# Autopilot2.net
KiCad netlist of a schematic drawn in EAGLE
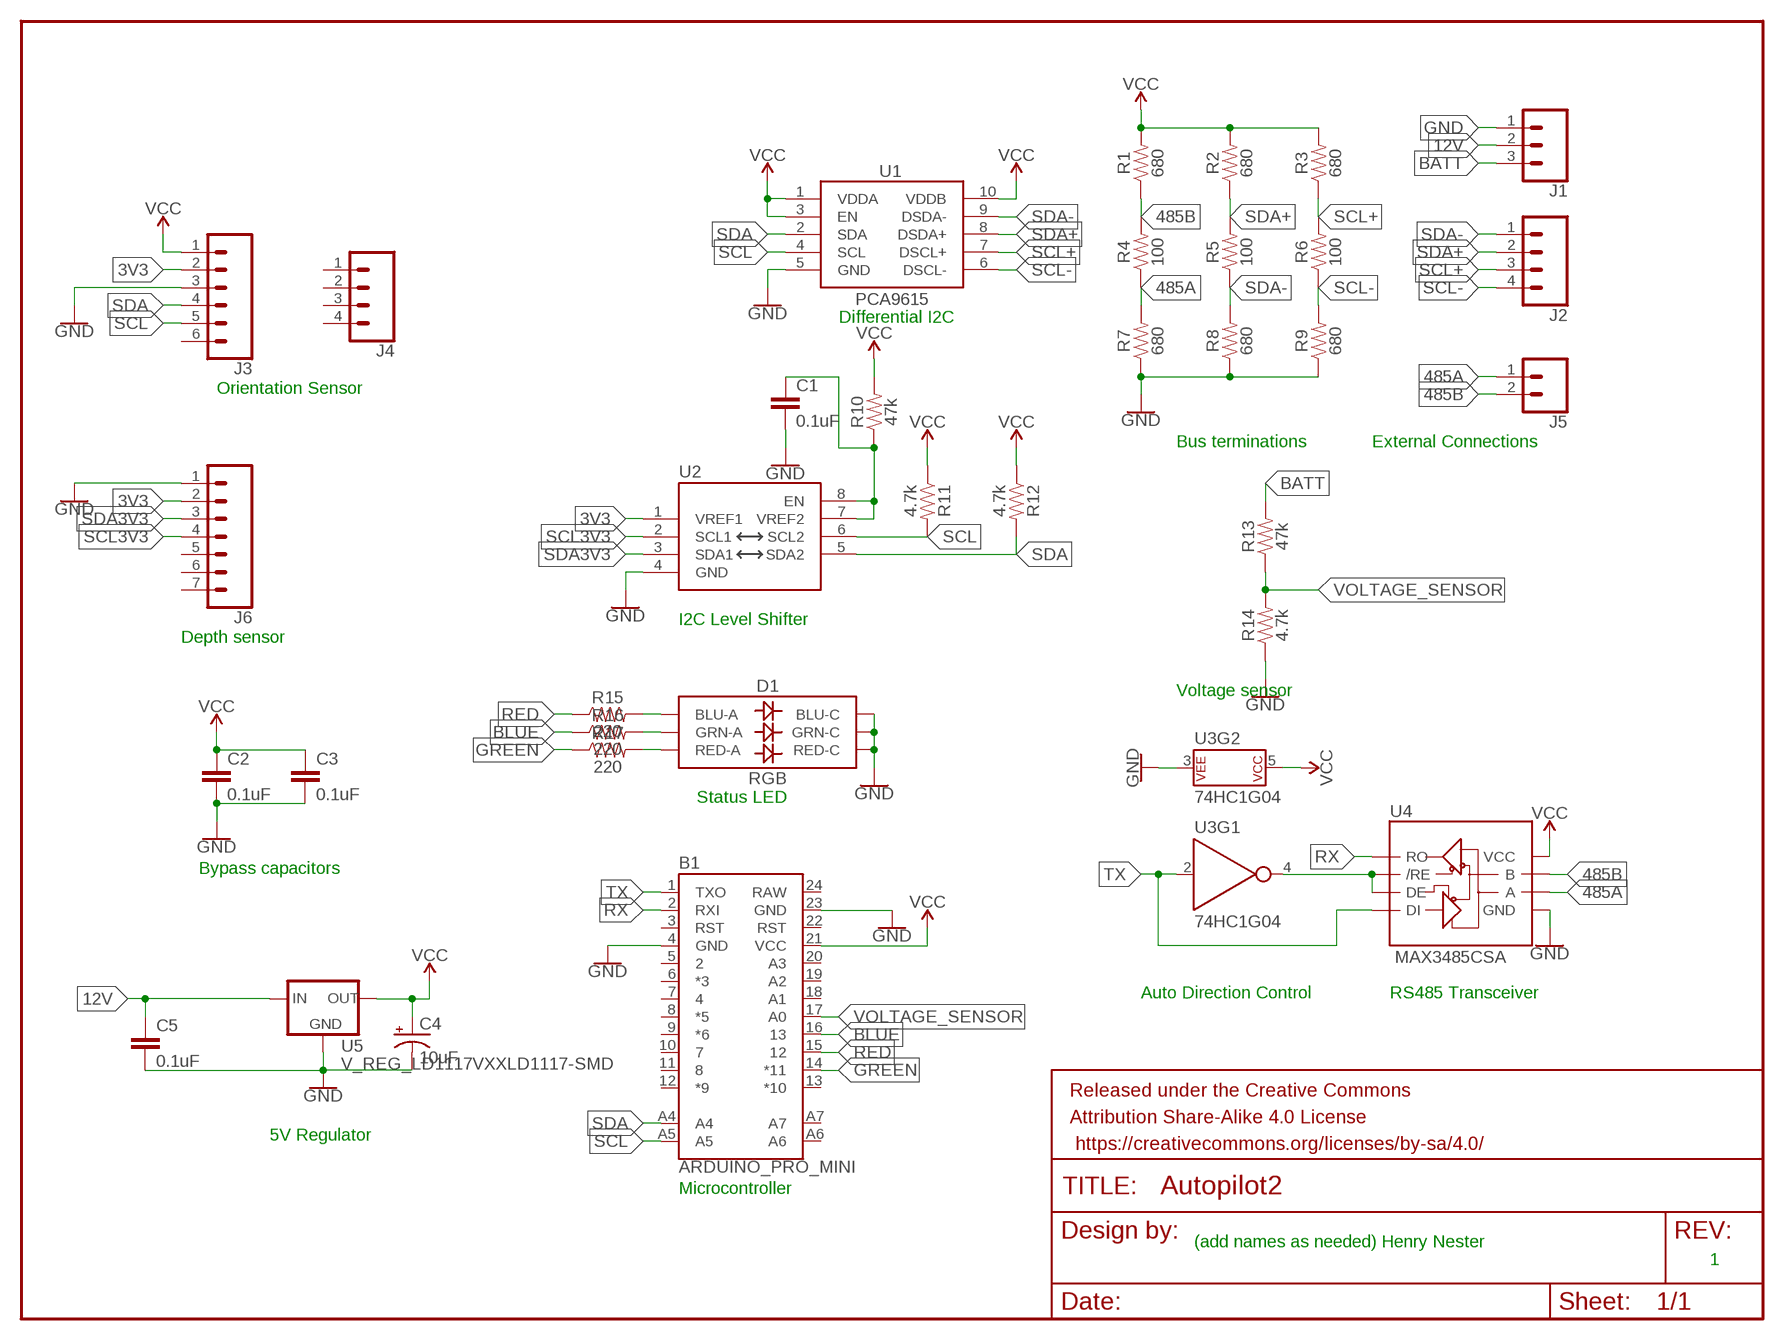
[diagram p0: schematic, sheet 1]

(export (version "E")
  (design (tool "Eeschema 10.0.6"))
  (components
    (comp (ref "B1")
      (value "ARDUINO_PRO_MINI")
      (footprint "eagle-import:ARDUINO_PRO_MINI")
      (libsource (lib "eagle-import") (part "ARDUINO_PRO_MINI"))
    )
    (comp (ref "C1")
      (value "0.1uF")
      (footprint "eagle-import:0603")
      (libsource (lib "eagle-import") (part "0.1UF-0603-25V-(+80/-20%)"))
    )
    (comp (ref "C2")
      (value "0.1uF")
      (footprint "eagle-import:0603")
      (libsource (lib "eagle-import") (part "0.1UF-0603-25V-(+80/-20%)"))
    )
    (comp (ref "C3")
      (value "0.1uF")
      (footprint "eagle-import:0603")
      (libsource (lib "eagle-import") (part "0.1UF-0603-25V-(+80/-20%)"))
    )
    (comp (ref "C4")
      (value "10uF")
      (footprint "eagle-import:CPOL-RADIAL-2.5MM-5MM")
      (libsource (lib "eagle-import") (part "10UF-POLAR-RADIAL-2.5MM-25V-20%"))
    )
    (comp (ref "C5")
      (value "0.1uF")
      (footprint "eagle-import:0603")
      (libsource (lib "eagle-import") (part "0.1UF-0603-25V-(+80/-20%)"))
    )
    (comp (ref "D1")
      (value "RGB")
      (footprint "eagle-import:PLCC-6-LED")
      (libsource (lib "eagle-import") (part "LED-RGBPLCC-6"))
    )
    (comp (ref "FRAME1")
      (value "FRAME-LETTERNO_PACKAGE")
      (footprint "eagle-import:DUMMY")
      (fields (field (name "DESIGNER") "Nobody"))
      (libsource (lib "eagle-import") (part "FRAME-LETTERNO_PACKAGE"))
    )
    (comp (ref "J1")
      (value "CONN_03LONGPADS")
      (footprint "eagle-import:1X03_LONGPADS")
      (libsource (lib "eagle-import") (part "CONN_03LONGPADS"))
    )
    (comp (ref "J2")
      (value "CONN_04")
      (footprint "eagle-import:1X04")
      (libsource (lib "eagle-import") (part "CONN_04"))
    )
    (comp (ref "J3")
      (value "CONN_06NO_SILK_FEMALE_PTH")
      (footprint "eagle-import:1X06_NO_SILK")
      (libsource (lib "eagle-import") (part "CONN_06NO_SILK_FEMALE_PTH"))
    )
    (comp (ref "J4")
      (value "CONN_041X04_NO_SILK")
      (footprint "eagle-import:1X04_NO_SILK")
      (libsource (lib "eagle-import") (part "CONN_041X04_NO_SILK"))
    )
    (comp (ref "J5")
      (value "CONN_02")
      (footprint "eagle-import:1X02")
      (libsource (lib "eagle-import") (part "CONN_02"))
    )
    (comp (ref "J6")
      (value "CONN_07NO_SILK")
      (footprint "eagle-import:1X07_NO_SILK")
      (libsource (lib "eagle-import") (part "CONN_07NO_SILK"))
    )
    (comp (ref "R1")
      (value "680")
      (footprint "eagle-import:0603")
      (libsource (lib "eagle-import") (part "680OHM-0603-1/10W-5%"))
    )
    (comp (ref "R2")
      (value "680")
      (footprint "eagle-import:0603")
      (libsource (lib "eagle-import") (part "680OHM-0603-1/10W-5%"))
    )
    (comp (ref "R3")
      (value "680")
      (footprint "eagle-import:0603")
      (libsource (lib "eagle-import") (part "680OHM-0603-1/10W-5%"))
    )
    (comp (ref "R4")
      (value "100")
      (footprint "eagle-import:0603")
      (libsource (lib "eagle-import") (part "100OHM-0603-1/4W-5%"))
    )
    (comp (ref "R5")
      (value "100")
      (footprint "eagle-import:0603")
      (libsource (lib "eagle-import") (part "100OHM-0603-1/4W-5%"))
    )
    (comp (ref "R6")
      (value "100")
      (footprint "eagle-import:0603")
      (libsource (lib "eagle-import") (part "100OHM-0603-1/4W-5%"))
    )
    (comp (ref "R7")
      (value "680")
      (footprint "eagle-import:0603")
      (libsource (lib "eagle-import") (part "680OHM-0603-1/10W-5%"))
    )
    (comp (ref "R8")
      (value "680")
      (footprint "eagle-import:0603")
      (libsource (lib "eagle-import") (part "680OHM-0603-1/10W-5%"))
    )
    (comp (ref "R9")
      (value "680")
      (footprint "eagle-import:0603")
      (libsource (lib "eagle-import") (part "680OHM-0603-1/10W-5%"))
    )
    (comp (ref "R10")
      (value "47k")
      (footprint "eagle-import:0603")
      (libsource (lib "eagle-import") (part "100KOHM-0603-1/10W-1%"))
    )
    (comp (ref "R11")
      (value "4.7k")
      (footprint "eagle-import:0603")
      (libsource (lib "eagle-import") (part "4.7KOHM-0603-1/10W-1%"))
    )
    (comp (ref "R12")
      (value "4.7k")
      (footprint "eagle-import:0603")
      (libsource (lib "eagle-import") (part "4.7KOHM-0603-1/10W-1%"))
    )
    (comp (ref "R13")
      (value "47k")
      (footprint "eagle-import:0603")
      (libsource (lib "eagle-import") (part "100KOHM-0603-1/10W-1%"))
    )
    (comp (ref "R14")
      (value "4.7k")
      (footprint "eagle-import:0603")
      (libsource (lib "eagle-import") (part "4.7KOHM-0603-1/10W-1%"))
    )
    (comp (ref "R15")
      (value "220")
      (footprint "eagle-import:0603")
      (libsource (lib "eagle-import") (part "220OHM-0603-1/10W-1%"))
    )
    (comp (ref "R16")
      (value "220")
      (footprint "eagle-import:0603")
      (libsource (lib "eagle-import") (part "220OHM-0603-1/10W-1%"))
    )
    (comp (ref "R17")
      (value "220")
      (footprint "eagle-import:0603")
      (libsource (lib "eagle-import") (part "220OHM-0603-1/10W-1%"))
    )
    (comp (ref "U1")
      (value "PCA9615")
      (footprint "eagle-import:TSSOP10")
      (libsource (lib "eagle-import") (part "PCA9615"))
    )
    (comp (ref "U2")
      (value "PCA9306MSOP-8")
      (footprint "eagle-import:MSOP8")
      (libsource (lib "eagle-import") (part "PCA9306MSOP-8"))
    )
    (comp (ref "U3")
      (value "74HC1G04")
      (footprint "eagle-import:SOT353")
      (libsource (lib "eagle-import") (part "741G04HC"))
    )
    (comp (ref "U4")
      (value "MAX3485CSA")
      (footprint "eagle-import:SO08")
      (libsource (lib "eagle-import") (part "RS485SOIC"))
    )
    (comp (ref "U5")
      (value "V_REG_LD1117VXXLD1117-SMD")
      (footprint "eagle-import:SOT223")
      (libsource (lib "eagle-import") (part "V_REG_LD1117VXXLD1117-SMD"))
    )
  )
  (nets
    (net (code "1") (name "/RAW") (class "Default")
      (node (ref "B1") (pin "24") (pinfunction "RAW_24") (pintype "power_in"))
    )
    (net (code "2") (name "3V3") (class "Default")
      (node (ref "J3") (pin "2") (pinfunction "2_2") (pintype "passive"))
      (node (ref "J6") (pin "2") (pinfunction "2_2") (pintype "passive"))
      (node (ref "U2") (pin "1") (pinfunction "VREF1_1") (pintype "bidirectional"))
    )
    (net (code "3") (name "12V") (class "Default")
      (node (ref "C5") (pin "1") (pinfunction "1_1") (pintype "passive"))
      (node (ref "J1") (pin "2") (pinfunction "2_2") (pintype "passive"))
      (node (ref "U5") (pin "3") (pinfunction "IN_3") (pintype "input"))
    )
    (net (code "4") (name "485A") (class "Default")
      (node (ref "J5") (pin "1") (pinfunction "1_1") (pintype "passive"))
      (node (ref "R4") (pin "1") (pinfunction "1_1") (pintype "passive"))
      (node (ref "R7") (pin "2") (pinfunction "2_2") (pintype "passive"))
      (node (ref "U4") (pin "6") (pinfunction "A_6") (pintype "bidirectional"))
    )
    (net (code "5") (name "485B") (class "Default")
      (node (ref "J5") (pin "2") (pinfunction "2_2") (pintype "passive"))
      (node (ref "R1") (pin "1") (pinfunction "1_1") (pintype "passive"))
      (node (ref "R4") (pin "2") (pinfunction "2_2") (pintype "passive"))
      (node (ref "U4") (pin "7") (pinfunction "B_7") (pintype "bidirectional"))
    )
    (net (code "6") (name "BATT") (class "Default")
      (node (ref "J1") (pin "3") (pinfunction "3_3") (pintype "passive"))
      (node (ref "R13") (pin "2") (pinfunction "2_2") (pintype "passive"))
    )
    (net (code "7") (name "BLUE") (class "Default")
      (node (ref "B1") (pin "16") (pinfunction "13_16") (pintype "bidirectional"))
      (node (ref "R16") (pin "1") (pinfunction "1_1") (pintype "passive"))
    )
    (net (code "8") (name "GND") (class "Default")
      (node (ref "B1") (pin "23") (pinfunction "GND_23") (pintype "power_in"))
      (node (ref "B1") (pin "4") (pinfunction "GND_4") (pintype "power_in"))
      (node (ref "C1") (pin "2") (pinfunction "2_2") (pintype "passive"))
      (node (ref "C2") (pin "2") (pinfunction "2_2") (pintype "passive"))
      (node (ref "C3") (pin "2") (pinfunction "2_2") (pintype "passive"))
      (node (ref "C4") (pin "2") (pinfunction "-_2") (pintype "passive"))
      (node (ref "C5") (pin "2") (pinfunction "2_2") (pintype "passive"))
      (node (ref "D1") (pin "CB") (pinfunction "BLU-C_CB") (pintype "bidirectional"))
      (node (ref "D1") (pin "CG") (pinfunction "GRN-C_CG") (pintype "bidirectional"))
      (node (ref "D1") (pin "CR") (pinfunction "RED-C_CR") (pintype "bidirectional"))
      (node (ref "J1") (pin "1") (pinfunction "1_1") (pintype "passive"))
      (node (ref "J3") (pin "3") (pinfunction "3_3") (pintype "passive"))
      (node (ref "J6") (pin "1") (pinfunction "1_1") (pintype "passive"))
      (node (ref "R14") (pin "1") (pinfunction "1_1") (pintype "passive"))
      (node (ref "R7") (pin "1") (pinfunction "1_1") (pintype "passive"))
      (node (ref "R8") (pin "1") (pinfunction "1_1") (pintype "passive"))
      (node (ref "R9") (pin "1") (pinfunction "1_1") (pintype "passive"))
      (node (ref "U1") (pin "5") (pinfunction "GND_5") (pintype "bidirectional"))
      (node (ref "U2") (pin "4") (pinfunction "GND_4") (pintype "bidirectional"))
      (node (ref "U3") (pin "3") (pinfunction "P$V-_3") (pintype "bidirectional"))
      (node (ref "U4") (pin "5") (pinfunction "GND_5") (pintype "bidirectional"))
      (node (ref "U5") (pin "1") (pinfunction "GND_1") (pintype "input"))
    )
    (net (code "9") (name "GREEN") (class "Default")
      (node (ref "B1") (pin "14") (pinfunction "*11_14") (pintype "bidirectional"))
      (node (ref "R17") (pin "1") (pinfunction "1_1") (pintype "passive"))
    )
    (net (code "10") (name "Net-(D1-BLU-A)") (class "Default")
      (node (ref "D1") (pin "AB") (pinfunction "BLU-A_AB") (pintype "bidirectional"))
      (node (ref "R15") (pin "2") (pinfunction "2_2") (pintype "passive"))
    )
    (net (code "11") (name "Net-(D1-GRN-A)") (class "Default")
      (node (ref "D1") (pin "AG") (pinfunction "GRN-A_AG") (pintype "bidirectional"))
      (node (ref "R16") (pin "2") (pinfunction "2_2") (pintype "passive"))
    )
    (net (code "12") (name "Net-(D1-RED-A)") (class "Default")
      (node (ref "D1") (pin "AR") (pinfunction "RED-A_AR") (pintype "bidirectional"))
      (node (ref "R17") (pin "2") (pinfunction "2_2") (pintype "passive"))
    )
    (net (code "13") (name "Net-(U2-EN)") (class "Default")
      (node (ref "C1") (pin "1") (pinfunction "1_1") (pintype "passive"))
      (node (ref "R10") (pin "1") (pinfunction "1_1") (pintype "passive"))
      (node (ref "U2") (pin "7") (pinfunction "VREF2_7") (pintype "bidirectional"))
      (node (ref "U2") (pin "8") (pinfunction "EN_8") (pintype "bidirectional"))
    )
    (net (code "14") (name "Net-(U3A-Y)") (class "Default")
      (node (ref "U3") (pin "4") (pinfunction "Y_4") (pintype "bidirectional"))
      (node (ref "U4") (pin "2") (pinfunction "/RE_2") (pintype "bidirectional"))
      (node (ref "U4") (pin "3") (pinfunction "DE_3") (pintype "bidirectional"))
    )
    (net (code "15") (name "RED") (class "Default")
      (node (ref "B1") (pin "15") (pinfunction "12_15") (pintype "bidirectional"))
      (node (ref "R15") (pin "1") (pinfunction "1_1") (pintype "passive"))
    )
    (net (code "16") (name "RX") (class "Default")
      (node (ref "B1") (pin "2") (pinfunction "RXI_2") (pintype "bidirectional"))
      (node (ref "U4") (pin "1") (pinfunction "RO_1") (pintype "bidirectional"))
    )
    (net (code "17") (name "SCL") (class "Default")
      (node (ref "B1") (pin "A5") (pinfunction "A5_A5") (pintype "bidirectional"))
      (node (ref "J3") (pin "5") (pinfunction "5_5") (pintype "passive"))
      (node (ref "R11") (pin "2") (pinfunction "2_2") (pintype "passive"))
      (node (ref "U1") (pin "4") (pinfunction "SCL_4") (pintype "bidirectional"))
      (node (ref "U2") (pin "6") (pinfunction "SCL2_6") (pintype "bidirectional"))
    )
    (net (code "18") (name "SCL+") (class "Default")
      (node (ref "J2") (pin "3") (pinfunction "3_3") (pintype "passive"))
      (node (ref "R3") (pin "1") (pinfunction "1_1") (pintype "passive"))
      (node (ref "R6") (pin "2") (pinfunction "2_2") (pintype "passive"))
      (node (ref "U1") (pin "7") (pinfunction "DSCL+_7") (pintype "bidirectional"))
    )
    (net (code "19") (name "SCL-") (class "Default")
      (node (ref "J2") (pin "4") (pinfunction "4_4") (pintype "passive"))
      (node (ref "R6") (pin "1") (pinfunction "1_1") (pintype "passive"))
      (node (ref "R9") (pin "2") (pinfunction "2_2") (pintype "passive"))
      (node (ref "U1") (pin "6") (pinfunction "DSCL-_6") (pintype "bidirectional"))
    )
    (net (code "20") (name "SCL3V3") (class "Default")
      (node (ref "J6") (pin "4") (pinfunction "4_4") (pintype "passive"))
      (node (ref "U2") (pin "2") (pinfunction "SCL1_2") (pintype "bidirectional"))
    )
    (net (code "21") (name "SDA") (class "Default")
      (node (ref "B1") (pin "A4") (pinfunction "A4_A4") (pintype "bidirectional"))
      (node (ref "J3") (pin "4") (pinfunction "4_4") (pintype "passive"))
      (node (ref "R12") (pin "2") (pinfunction "2_2") (pintype "passive"))
      (node (ref "U1") (pin "2") (pinfunction "SDA_2") (pintype "bidirectional"))
      (node (ref "U2") (pin "5") (pinfunction "SDA2_5") (pintype "bidirectional"))
    )
    (net (code "22") (name "SDA+") (class "Default")
      (node (ref "J2") (pin "2") (pinfunction "2_2") (pintype "passive"))
      (node (ref "R2") (pin "1") (pinfunction "1_1") (pintype "passive"))
      (node (ref "R5") (pin "2") (pinfunction "2_2") (pintype "passive"))
      (node (ref "U1") (pin "8") (pinfunction "DSDA+_8") (pintype "bidirectional"))
    )
    (net (code "23") (name "SDA-") (class "Default")
      (node (ref "J2") (pin "1") (pinfunction "1_1") (pintype "passive"))
      (node (ref "R5") (pin "1") (pinfunction "1_1") (pintype "passive"))
      (node (ref "R8") (pin "2") (pinfunction "2_2") (pintype "passive"))
      (node (ref "U1") (pin "9") (pinfunction "DSDA-_9") (pintype "bidirectional"))
    )
    (net (code "24") (name "SDA3V3") (class "Default")
      (node (ref "J6") (pin "3") (pinfunction "3_3") (pintype "passive"))
      (node (ref "U2") (pin "3") (pinfunction "SDA1_3") (pintype "bidirectional"))
    )
    (net (code "25") (name "TX") (class "Default")
      (node (ref "B1") (pin "1") (pinfunction "TXO_1") (pintype "bidirectional"))
      (node (ref "U3") (pin "2") (pinfunction "A_2") (pintype "bidirectional"))
      (node (ref "U4") (pin "4") (pinfunction "DI_4") (pintype "bidirectional"))
    )
    (net (code "26") (name "VCC") (class "Default")
      (node (ref "B1") (pin "21") (pinfunction "VCC_21") (pintype "power_in"))
      (node (ref "C2") (pin "1") (pinfunction "1_1") (pintype "passive"))
      (node (ref "C3") (pin "1") (pinfunction "1_1") (pintype "passive"))
      (node (ref "C4") (pin "1") (pinfunction "+_1") (pintype "passive"))
      (node (ref "J3") (pin "1") (pinfunction "1_1") (pintype "passive"))
      (node (ref "R1") (pin "2") (pinfunction "2_2") (pintype "passive"))
      (node (ref "R10") (pin "2") (pinfunction "2_2") (pintype "passive"))
      (node (ref "R11") (pin "1") (pinfunction "1_1") (pintype "passive"))
      (node (ref "R12") (pin "1") (pinfunction "1_1") (pintype "passive"))
      (node (ref "R2") (pin "2") (pinfunction "2_2") (pintype "passive"))
      (node (ref "R3") (pin "2") (pinfunction "2_2") (pintype "passive"))
      (node (ref "U1") (pin "1") (pinfunction "VDDA_1") (pintype "bidirectional"))
      (node (ref "U1") (pin "10") (pinfunction "VDDB_10") (pintype "bidirectional"))
      (node (ref "U1") (pin "3") (pinfunction "EN_3") (pintype "bidirectional"))
      (node (ref "U3") (pin "5") (pinfunction "P$V+_5") (pintype "bidirectional"))
      (node (ref "U4") (pin "8") (pinfunction "VCC_8") (pintype "bidirectional"))
      (node (ref "U5") (pin "2") (pinfunction "OUT_2") (pintype "passive"))
    )
    (net (code "27") (name "VOLTAGE_SENSOR") (class "Default")
      (node (ref "B1") (pin "17") (pinfunction "A0_17") (pintype "bidirectional"))
      (node (ref "R13") (pin "1") (pinfunction "1_1") (pintype "passive"))
      (node (ref "R14") (pin "2") (pinfunction "2_2") (pintype "passive"))
    )
    (net (code "28") (name "unconnected-(B1-*3-Pad6)") (class "Default")
      (node (ref "B1") (pin "6") (pinfunction "*3_6") (pintype "bidirectional"))
    )
    (net (code "29") (name "unconnected-(B1-*5-Pad8)") (class "Default")
      (node (ref "B1") (pin "8") (pinfunction "*5_8") (pintype "bidirectional"))
    )
    (net (code "30") (name "unconnected-(B1-*6-Pad9)") (class "Default")
      (node (ref "B1") (pin "9") (pinfunction "*6_9") (pintype "bidirectional"))
    )
    (net (code "31") (name "unconnected-(B1-*9-Pad12)") (class "Default")
      (node (ref "B1") (pin "12") (pinfunction "*9_12") (pintype "bidirectional"))
    )
    (net (code "32") (name "unconnected-(B1-*10-Pad13)") (class "Default")
      (node (ref "B1") (pin "13") (pinfunction "*10_13") (pintype "bidirectional"))
    )
    (net (code "33") (name "unconnected-(B1-2-Pad5)") (class "Default")
      (node (ref "B1") (pin "5") (pinfunction "2_5") (pintype "bidirectional"))
    )
    (net (code "34") (name "unconnected-(B1-4-Pad7)") (class "Default")
      (node (ref "B1") (pin "7") (pinfunction "4_7") (pintype "bidirectional"))
    )
    (net (code "35") (name "unconnected-(B1-7-Pad10)") (class "Default")
      (node (ref "B1") (pin "10") (pinfunction "7_10") (pintype "bidirectional"))
    )
    (net (code "36") (name "unconnected-(B1-8-Pad11)") (class "Default")
      (node (ref "B1") (pin "11") (pinfunction "8_11") (pintype "bidirectional"))
    )
    (net (code "37") (name "unconnected-(B1-A1-Pad18)") (class "Default")
      (node (ref "B1") (pin "18") (pinfunction "A1_18") (pintype "bidirectional"))
    )
    (net (code "38") (name "unconnected-(B1-A2-Pad19)") (class "Default")
      (node (ref "B1") (pin "19") (pinfunction "A2_19") (pintype "bidirectional"))
    )
    (net (code "39") (name "unconnected-(B1-A3-Pad20)") (class "Default")
      (node (ref "B1") (pin "20") (pinfunction "A3_20") (pintype "bidirectional"))
    )
    (net (code "40") (name "unconnected-(B1-PadA6)") (class "Default")
      (node (ref "B1") (pin "A6") (pinfunction "A6_A6") (pintype "bidirectional"))
    )
    (net (code "41") (name "unconnected-(B1-PadA7)") (class "Default")
      (node (ref "B1") (pin "A7") (pinfunction "A7_A7") (pintype "bidirectional"))
    )
    (net (code "42") (name "unconnected-(B1-RST-Pad3)") (class "Default")
      (node (ref "B1") (pin "3") (pinfunction "RST_3") (pintype "bidirectional"))
    )
    (net (code "43") (name "unconnected-(B1-RST-Pad22)") (class "Default")
      (node (ref "B1") (pin "22") (pinfunction "RST_22") (pintype "bidirectional"))
    )
    (net (code "44") (name "unconnected-(J3-Pad6)") (class "Default")
      (node (ref "J3") (pin "6") (pinfunction "6_6") (pintype "passive"))
    )
    (net (code "45") (name "unconnected-(J4-Pad1)") (class "Default")
      (node (ref "J4") (pin "1") (pinfunction "1_1") (pintype "passive"))
    )
    (net (code "46") (name "unconnected-(J4-Pad2)") (class "Default")
      (node (ref "J4") (pin "2") (pinfunction "2_2") (pintype "passive"))
    )
    (net (code "47") (name "unconnected-(J4-Pad3)") (class "Default")
      (node (ref "J4") (pin "3") (pinfunction "3_3") (pintype "passive"))
    )
    (net (code "48") (name "unconnected-(J4-Pad4)") (class "Default")
      (node (ref "J4") (pin "4") (pinfunction "4_4") (pintype "passive"))
    )
    (net (code "49") (name "unconnected-(J6-Pad5)") (class "Default")
      (node (ref "J6") (pin "5") (pinfunction "5_5") (pintype "passive"))
    )
    (net (code "50") (name "unconnected-(J6-Pad6)") (class "Default")
      (node (ref "J6") (pin "6") (pinfunction "6_6") (pintype "passive"))
    )
    (net (code "51") (name "unconnected-(J6-Pad7)") (class "Default")
      (node (ref "J6") (pin "7") (pinfunction "7_7") (pintype "passive"))
    )
  )
)
